# SmartWatch-BASIC-TOP.net
KiCad netlist of a schematic drawn in EAGLE
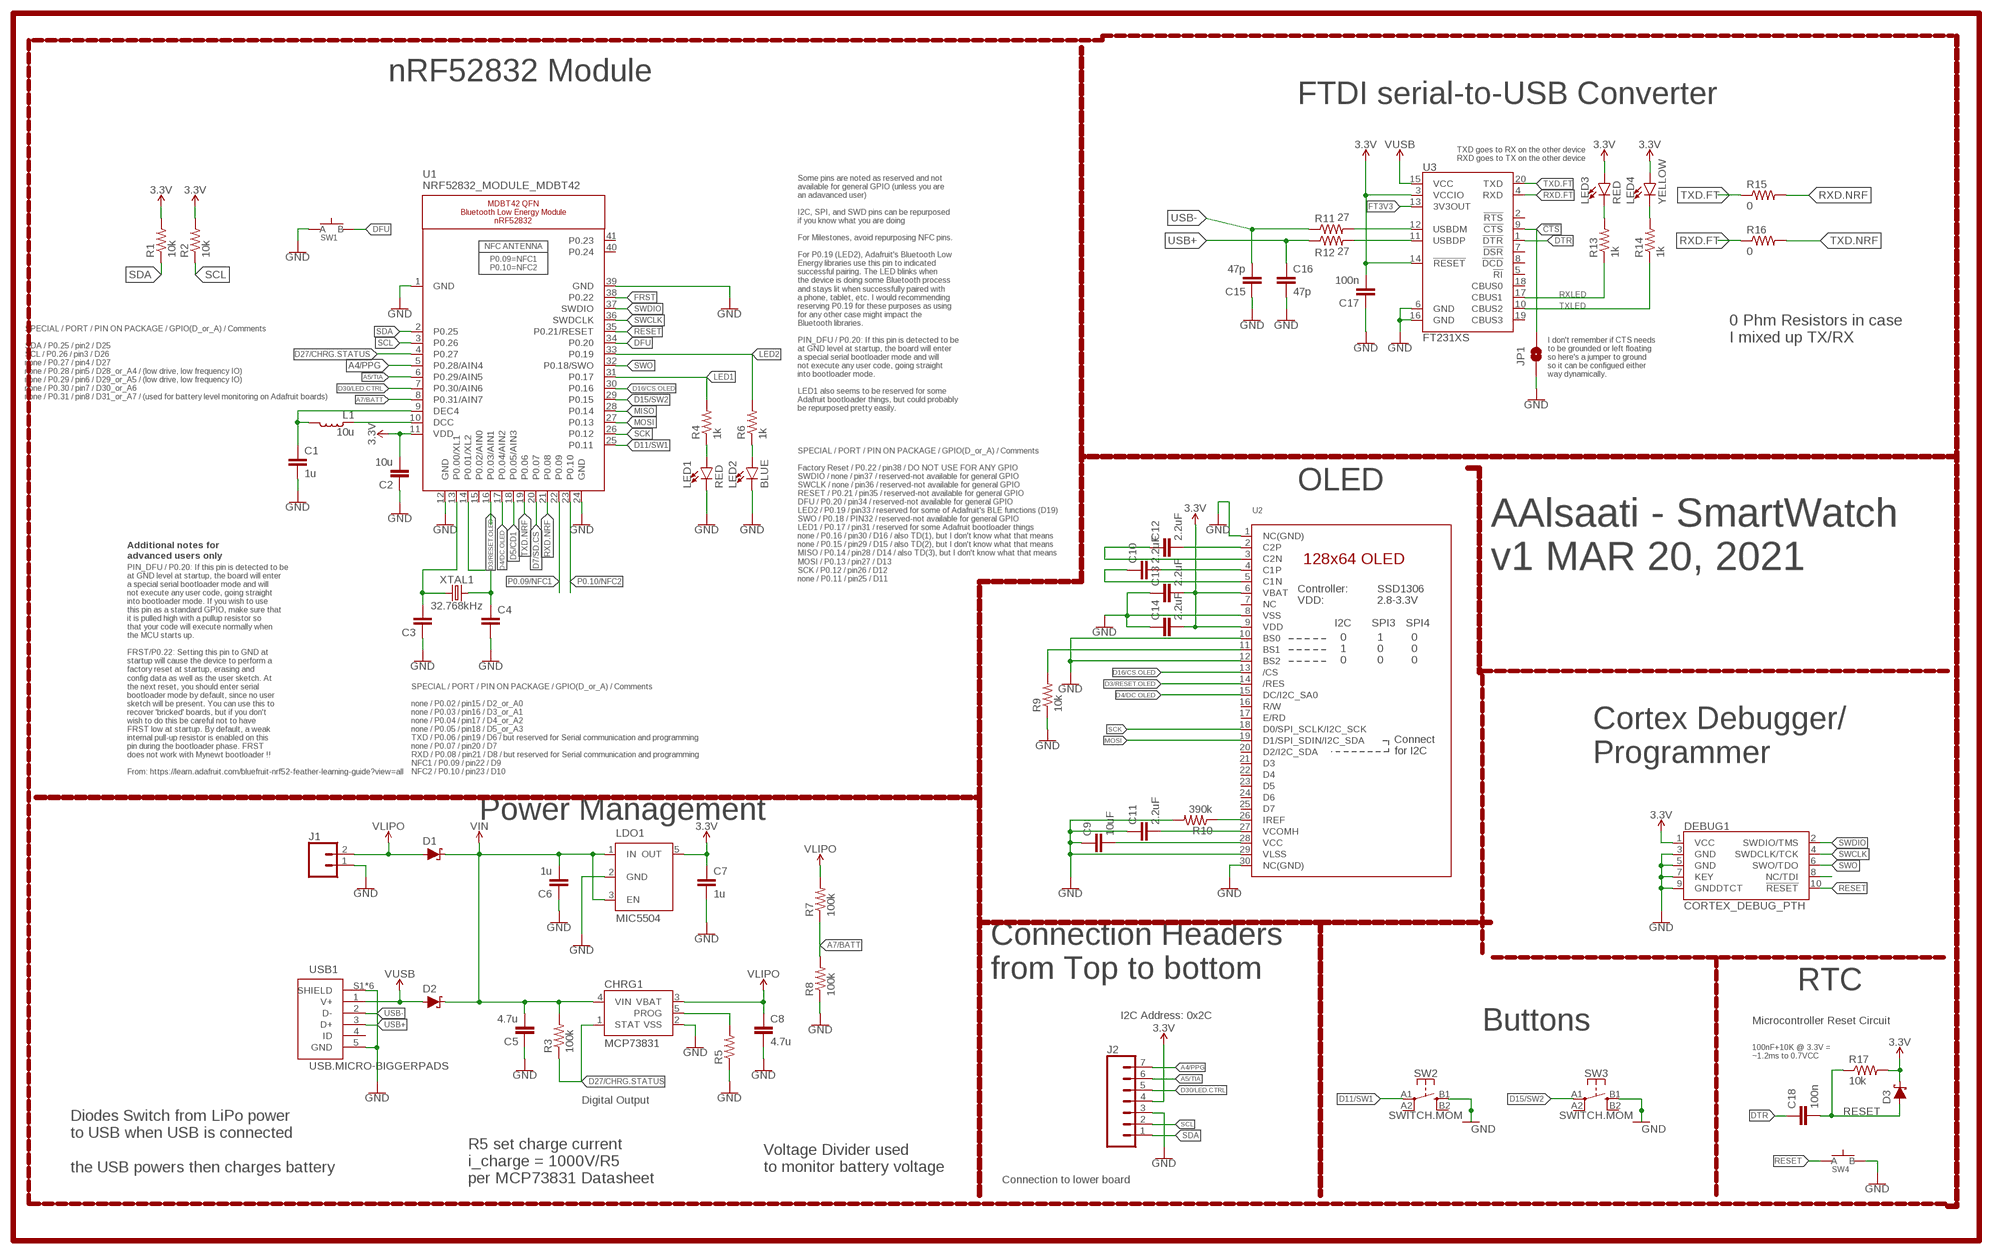
[diagram p0: schematic, sheet 1]

(export (version "E")
  (design (tool "Eeschema 10.0.6"))
  (components
    (comp (ref "C1")
      (value "1u")
      (footprint "eagle-import:C0603")
      (libsource (lib "eagle-import") (part "CAPACITOR0603"))
    )
    (comp (ref "C2")
      (value "10u")
      (footprint "eagle-import:C0805")
      (libsource (lib "eagle-import") (part "CAPACITOR0805"))
    )
    (comp (ref "C3")
      (value "CAPACITOR0603")
      (footprint "eagle-import:C0603")
      (libsource (lib "eagle-import") (part "CAPACITOR0603"))
    )
    (comp (ref "C4")
      (value "CAPACITOR0603")
      (footprint "eagle-import:C0603")
      (libsource (lib "eagle-import") (part "CAPACITOR0603"))
    )
    (comp (ref "C5")
      (value "4.7u")
      (footprint "eagle-import:C0603")
      (libsource (lib "eagle-import") (part "CAPACITOR0603"))
    )
    (comp (ref "C6")
      (value "1u")
      (footprint "eagle-import:C0603")
      (libsource (lib "eagle-import") (part "CAPACITOR0603"))
    )
    (comp (ref "C7")
      (value "1u")
      (footprint "eagle-import:C0603")
      (libsource (lib "eagle-import") (part "CAPACITOR0603"))
    )
    (comp (ref "C8")
      (value "4.7u")
      (footprint "eagle-import:C0603")
      (libsource (lib "eagle-import") (part "CAPACITOR0603"))
    )
    (comp (ref "C9")
      (value "10uF")
      (footprint "eagle-import:C0603")
      (libsource (lib "eagle-import") (part "CAPACITOR0603"))
    )
    (comp (ref "C10")
      (value "2.2uF")
      (footprint "eagle-import:C0402")
      (libsource (lib "eagle-import") (part "CAPACITOR0402"))
    )
    (comp (ref "C11")
      (value "2.2uF")
      (footprint "eagle-import:C0603")
      (libsource (lib "eagle-import") (part "CAPACITOR0603"))
    )
    (comp (ref "C12")
      (value "2.2uF")
      (footprint "eagle-import:C0402")
      (libsource (lib "eagle-import") (part "CAPACITOR0402"))
    )
    (comp (ref "C13")
      (value "2.2uF")
      (footprint "eagle-import:C0402")
      (libsource (lib "eagle-import") (part "CAPACITOR0402"))
    )
    (comp (ref "C14")
      (value "2.2uF")
      (footprint "eagle-import:C0402")
      (libsource (lib "eagle-import") (part "CAPACITOR0402"))
    )
    (comp (ref "C15")
      (value "47p")
      (footprint "eagle-import:C0603")
      (libsource (lib "eagle-import") (part "CAPACITOR0603"))
    )
    (comp (ref "C16")
      (value "47p")
      (footprint "eagle-import:C0603")
      (libsource (lib "eagle-import") (part "CAPACITOR0603"))
    )
    (comp (ref "C17")
      (value "100n")
      (footprint "eagle-import:C0603")
      (libsource (lib "eagle-import") (part "CAPACITOR0603"))
    )
    (comp (ref "C18")
      (value "100n")
      (footprint "eagle-import:C0603")
      (libsource (lib "eagle-import") (part "CAPACITOR0603"))
    )
    (comp (ref "CHRG1")
      (value "MCP73831")
      (footprint "eagle-import:SOT23-5")
      (libsource (lib "eagle-import") (part "MCP73831"))
    )
    (comp (ref "D1")
      (value "SCHOTTKY-USC")
      (footprint "eagle-import:USC")
      (libsource (lib "eagle-import") (part "SCHOTTKY-USC"))
    )
    (comp (ref "D2")
      (value "SCHOTTKY-USC")
      (footprint "eagle-import:USC")
      (libsource (lib "eagle-import") (part "SCHOTTKY-USC"))
    )
    (comp (ref "D3")
      (value "SCHOTTKY-USC")
      (footprint "eagle-import:USC")
      (libsource (lib "eagle-import") (part "SCHOTTKY-USC"))
    )
    (comp (ref "DEBUG1")
      (value "CORTEX_DEBUG_PTH")
      (footprint "eagle-import:2X5-PTH-1.27MM")
      (libsource (lib "eagle-import") (part "CORTEX_DEBUG_PTH"))
    )
    (comp (ref "J1")
      (value "CONN_02")
      (footprint "eagle-import:1X02")
      (libsource (lib "eagle-import") (part "CONN_02"))
    )
    (comp (ref "J2")
      (value "CONN_07-1.27MM")
      (footprint "eagle-import:1X07_1.27MM")
      (libsource (lib "eagle-import") (part "CONN_07-1.27MM"))
    )
    (comp (ref "JP1")
      (value "JUMPER-SMT_2_NO_SILK")
      (footprint "eagle-import:SMT-JUMPER_2_NO_SILK")
      (libsource (lib "eagle-import") (part "JUMPER-SMT_2_NO_SILK"))
    )
    (comp (ref "L1")
      (value "10u")
      (footprint "eagle-import:L0603")
      (libsource (lib "eagle-import") (part "INDUCTOR0603"))
    )
    (comp (ref "LDO1")
      (value "MIC5504")
      (footprint "eagle-import:SOT23-5")
      (libsource (lib "eagle-import") (part "MIC5504"))
    )
    (comp (ref "LED1")
      (value "RED")
      (footprint "eagle-import:LED-0603")
      (libsource (lib "eagle-import") (part "LED0603"))
    )
    (comp (ref "LED2")
      (value "BLUE")
      (footprint "eagle-import:LED-0603")
      (libsource (lib "eagle-import") (part "LED0603"))
    )
    (comp (ref "LED3")
      (value "RED")
      (footprint "eagle-import:LED-0603")
      (libsource (lib "eagle-import") (part "LED0603"))
    )
    (comp (ref "LED4")
      (value "YELLOW")
      (footprint "eagle-import:LED-0603")
      (libsource (lib "eagle-import") (part "LED0603"))
    )
    (comp (ref "R1")
      (value "10k")
      (footprint "eagle-import:R0603")
      (libsource (lib "eagle-import") (part "RESISTOR0603"))
    )
    (comp (ref "R2")
      (value "10k")
      (footprint "eagle-import:R0603")
      (libsource (lib "eagle-import") (part "RESISTOR0603"))
    )
    (comp (ref "R3")
      (value "100k")
      (footprint "eagle-import:R0603")
      (libsource (lib "eagle-import") (part "RESISTOR0603"))
    )
    (comp (ref "R4")
      (value "1k")
      (footprint "eagle-import:R0603")
      (libsource (lib "eagle-import") (part "RESISTOR0603"))
    )
    (comp (ref "R5")
      (value "RESISTOR0603")
      (footprint "eagle-import:R0603")
      (libsource (lib "eagle-import") (part "RESISTOR0603"))
    )
    (comp (ref "R6")
      (value "1k")
      (footprint "eagle-import:R0603")
      (libsource (lib "eagle-import") (part "RESISTOR0603"))
    )
    (comp (ref "R7")
      (value "100k")
      (footprint "eagle-import:R0603")
      (libsource (lib "eagle-import") (part "RESISTOR0603"))
    )
    (comp (ref "R8")
      (value "100k")
      (footprint "eagle-import:R0603")
      (libsource (lib "eagle-import") (part "RESISTOR0603"))
    )
    (comp (ref "R9")
      (value "10k")
      (footprint "eagle-import:R0603")
      (libsource (lib "eagle-import") (part "RESISTOR0603"))
    )
    (comp (ref "R10")
      (value "390k")
      (footprint "eagle-import:R0603")
      (libsource (lib "eagle-import") (part "RESISTOR0603"))
    )
    (comp (ref "R11")
      (value "27")
      (footprint "eagle-import:R0603")
      (libsource (lib "eagle-import") (part "RESISTOR0603"))
    )
    (comp (ref "R12")
      (value "27")
      (footprint "eagle-import:R0603")
      (libsource (lib "eagle-import") (part "RESISTOR0603"))
    )
    (comp (ref "R13")
      (value "1k")
      (footprint "eagle-import:R0603")
      (libsource (lib "eagle-import") (part "RESISTOR0603"))
    )
    (comp (ref "R14")
      (value "1k")
      (footprint "eagle-import:R0603")
      (libsource (lib "eagle-import") (part "RESISTOR0603"))
    )
    (comp (ref "R15")
      (value "0")
      (footprint "eagle-import:R0603")
      (libsource (lib "eagle-import") (part "RESISTOR0603"))
    )
    (comp (ref "R16")
      (value "0")
      (footprint "eagle-import:R0603")
      (libsource (lib "eagle-import") (part "RESISTOR0603"))
    )
    (comp (ref "R17")
      (value "10k")
      (footprint "eagle-import:R0603")
      (libsource (lib "eagle-import") (part "RESISTOR0603"))
    )
    (comp (ref "SW1")
      (value "SPST-PTS830GG140-COPY.1-3")
      (footprint "eagle-import:BUTTON-GULLWING")
      (libsource (lib "eagle-import") (part "SPST-PTS830GG140-COPY.1-3"))
    )
    (comp (ref "SW2")
      (value "SWITCH.MOM")
      (footprint "eagle-import:TACTILE_SWITCH_SMD_6.2MM_TALL")
      (libsource (lib "eagle-import") (part "SWITCH.MOM"))
    )
    (comp (ref "SW3")
      (value "SWITCH.MOM")
      (footprint "eagle-import:TACTILE_SWITCH_SMD_6.2MM_TALL")
      (libsource (lib "eagle-import") (part "SWITCH.MOM"))
    )
    (comp (ref "SW4")
      (value "SPST-PTS830GG140-COPY.1-3")
      (footprint "eagle-import:BUTTON-GULLWING")
      (libsource (lib "eagle-import") (part "SPST-PTS830GG140-COPY.1-3"))
    )
    (comp (ref "U1")
      (value "NRF52832_MODULE_MDBT42")
      (footprint "eagle-import:BLE_MODULE_RAYTAC_MDBT42")
      (libsource (lib "eagle-import") (part "NRF52832_MODULE_MDBT42"))
    )
    (comp (ref "U2")
      (value "DISP_OLED_UG-2864HSWEG01-NO-WRAPAROUND")
      (footprint "eagle-import:UG-2864HSWEG01_0.96IN_NO-WRAPAROUND")
      (libsource (lib "eagle-import") (part "DISP_OLED_UG-2864HSWEG01-NO-WRAPAROUND"))
    )
    (comp (ref "U3")
      (value "FT231XS")
      (footprint "eagle-import:SSOP20_L")
      (libsource (lib "eagle-import") (part "FT231XS"))
    )
    (comp (ref "USB1")
      (value "USB.MICRO-BIGGERPADS")
      (footprint "eagle-import:USB-MICRO-01.BIGGERPADS")
      (libsource (lib "eagle-import") (part "USB.MICRO-BIGGERPADS"))
    )
    (comp (ref "XTAL1")
      (value "32.768kHz")
      (footprint "eagle-import:2-SMD.NOLEAD.2.0MMTO1.2MM")
      (libsource (lib "eagle-import") (part "CRYSTALECS-.327-12.5-12-C-TR"))
    )
  )
  (nets
    (net (code "1") (name "/RXLED") (class "Default")
      (node (ref "R13") (pin "1") (pinfunction "1_1") (pintype "passive"))
      (node (ref "U3") (pin "17") (pinfunction "CBUS1_17") (pintype "bidirectional"))
    )
    (net (code "2") (name "/TXLED") (class "Default")
      (node (ref "R14") (pin "1") (pinfunction "1_1") (pintype "passive"))
      (node (ref "U3") (pin "10") (pinfunction "CBUS2_10") (pintype "bidirectional"))
    )
    (net (code "3") (name "/~{CTS}") (class "Default")
      (node (ref "JP1") (pin "2") (pinfunction "2_2") (pintype "passive"))
      (node (ref "U3") (pin "9") (pinfunction "~{CTS}_9") (pintype "bidirectional"))
    )
    (net (code "4") (name "3.3V") (class "Default")
      (node (ref "C13") (pin "2") (pinfunction "2_2") (pintype "passive"))
      (node (ref "C14") (pin "2") (pinfunction "2_2") (pintype "passive"))
      (node (ref "C17") (pin "2") (pinfunction "2_2") (pintype "passive"))
      (node (ref "C2") (pin "2") (pinfunction "2_2") (pintype "passive"))
      (node (ref "C7") (pin "1") (pinfunction "1_1") (pintype "passive"))
      (node (ref "D3") (pin "-") (pinfunction "C_-") (pintype "passive"))
      (node (ref "DEBUG1") (pin "1") (pinfunction "VCC_1") (pintype "bidirectional"))
      (node (ref "J2") (pin "4") (pinfunction "4_4") (pintype "passive"))
      (node (ref "LDO1") (pin "5") (pinfunction "OUT_5") (pintype "bidirectional"))
      (node (ref "LED3") (pin "A") (pinfunction "A_A") (pintype "passive"))
      (node (ref "LED4") (pin "A") (pinfunction "A_A") (pintype "passive"))
      (node (ref "R1") (pin "2") (pinfunction "2_2") (pintype "passive"))
      (node (ref "R17") (pin "2") (pinfunction "2_2") (pintype "passive"))
      (node (ref "R2") (pin "2") (pinfunction "2_2") (pintype "passive"))
      (node (ref "U1") (pin "11") (pinfunction "VDD_11") (pintype "bidirectional"))
      (node (ref "U2") (pin "6") (pinfunction "VBAT_6") (pintype "input"))
      (node (ref "U2") (pin "9") (pinfunction "VDD_9") (pintype "power_in"))
      (node (ref "U3") (pin "14") (pinfunction "~{RESET}_14") (pintype "bidirectional"))
      (node (ref "U3") (pin "3") (pinfunction "VCCIO_3") (pintype "bidirectional"))
    )
    (net (code "5") (name "A4{slash}PPG") (class "Default")
      (node (ref "J2") (pin "7") (pinfunction "7_7") (pintype "passive"))
      (node (ref "U1") (pin "5") (pinfunction "P0.28/AIN4_5") (pintype "bidirectional"))
    )
    (net (code "6") (name "A5{slash}TIA") (class "Default")
      (node (ref "J2") (pin "6") (pinfunction "6_6") (pintype "passive"))
      (node (ref "U1") (pin "6") (pinfunction "P0.29/AIN5_6") (pintype "bidirectional"))
    )
    (net (code "7") (name "A7{slash}BATT") (class "Default")
      (node (ref "R7") (pin "1") (pinfunction "1_1") (pintype "passive"))
      (node (ref "R8") (pin "2") (pinfunction "2_2") (pintype "passive"))
      (node (ref "U1") (pin "8") (pinfunction "P0.31/AIN7_8") (pintype "bidirectional"))
    )
    (net (code "8") (name "D3{slash}RESET.OLED") (class "Default")
      (node (ref "U1") (pin "16") (pinfunction "P0.03/AIN1_16") (pintype "bidirectional"))
      (node (ref "U2") (pin "14") (pinfunction "/RES_14") (pintype "input"))
    )
    (net (code "9") (name "D4{slash}DC.OLED") (class "Default")
      (node (ref "U1") (pin "17") (pinfunction "P0.04/AIN2_17") (pintype "bidirectional"))
      (node (ref "U2") (pin "15") (pinfunction "DC/I2C_SA0_15") (pintype "input"))
    )
    (net (code "10") (name "D5{slash}CD1") (class "Default")
      (node (ref "U1") (pin "18") (pinfunction "P0.05/AIN3_18") (pintype "bidirectional"))
    )
    (net (code "11") (name "D7{slash}SD.CS") (class "Default")
      (node (ref "U1") (pin "20") (pinfunction "P0.07_20") (pintype "bidirectional"))
    )
    (net (code "12") (name "D11{slash}SW1") (class "Default")
      (node (ref "SW2") (pin "A1") (pinfunction "1_A1") (pintype "passive"))
      (node (ref "U1") (pin "25") (pinfunction "P0.11_25") (pintype "bidirectional"))
    )
    (net (code "13") (name "D15{slash}SW2") (class "Default")
      (node (ref "SW3") (pin "A1") (pinfunction "1_A1") (pintype "passive"))
      (node (ref "U1") (pin "29") (pinfunction "P0.15_29") (pintype "bidirectional"))
    )
    (net (code "14") (name "D16{slash}CS.OLED") (class "Default")
      (node (ref "U1") (pin "30") (pinfunction "P0.16_30") (pintype "bidirectional"))
      (node (ref "U2") (pin "13") (pinfunction "/CS_13") (pintype "input"))
    )
    (net (code "15") (name "D27{slash}CHRG.STATUS") (class "Default")
      (node (ref "CHRG1") (pin "1") (pinfunction "STAT_1") (pintype "output"))
      (node (ref "R3") (pin "1") (pinfunction "1_1") (pintype "passive"))
      (node (ref "U1") (pin "4") (pinfunction "P0.27_4") (pintype "bidirectional"))
    )
    (net (code "16") (name "D30{slash}LED.CTRL") (class "Default")
      (node (ref "J2") (pin "5") (pinfunction "5_5") (pintype "passive"))
      (node (ref "U1") (pin "7") (pinfunction "P0.30/AIN6_7") (pintype "bidirectional"))
    )
    (net (code "17") (name "DFU") (class "Default")
      (node (ref "SW1") (pin "3") (pinfunction "B_3") (pintype "bidirectional"))
      (node (ref "U1") (pin "34") (pinfunction "P0.20_34") (pintype "bidirectional"))
    )
    (net (code "18") (name "DTR") (class "Default")
      (node (ref "C18") (pin "1") (pinfunction "1_1") (pintype "passive"))
      (node (ref "U3") (pin "1") (pinfunction "~{DTR}_1") (pintype "bidirectional"))
    )
    (net (code "19") (name "FRST") (class "Default")
      (node (ref "U1") (pin "38") (pinfunction "P0.22_38") (pintype "bidirectional"))
    )
    (net (code "20") (name "FT3V3") (class "Default")
      (node (ref "U3") (pin "13") (pinfunction "3V3OUT_13") (pintype "bidirectional"))
    )
    (net (code "21") (name "GND") (class "Default")
      (node (ref "C1") (pin "2") (pinfunction "2_2") (pintype "passive"))
      (node (ref "C11") (pin "1") (pinfunction "1_1") (pintype "passive"))
      (node (ref "C13") (pin "1") (pinfunction "1_1") (pintype "passive"))
      (node (ref "C14") (pin "1") (pinfunction "1_1") (pintype "passive"))
      (node (ref "C15") (pin "1") (pinfunction "1_1") (pintype "passive"))
      (node (ref "C16") (pin "2") (pinfunction "2_2") (pintype "passive"))
      (node (ref "C17") (pin "1") (pinfunction "1_1") (pintype "passive"))
      (node (ref "C2") (pin "1") (pinfunction "1_1") (pintype "passive"))
      (node (ref "C3") (pin "1") (pinfunction "1_1") (pintype "passive"))
      (node (ref "C4") (pin "2") (pinfunction "2_2") (pintype "passive"))
      (node (ref "C5") (pin "1") (pinfunction "1_1") (pintype "passive"))
      (node (ref "C6") (pin "1") (pinfunction "1_1") (pintype "passive"))
      (node (ref "C7") (pin "2") (pinfunction "2_2") (pintype "passive"))
      (node (ref "C8") (pin "2") (pinfunction "2_2") (pintype "passive"))
      (node (ref "C9") (pin "1") (pinfunction "1_1") (pintype "passive"))
      (node (ref "CHRG1") (pin "2") (pinfunction "VSS_2") (pintype "power_in"))
      (node (ref "DEBUG1") (pin "3") (pinfunction "GND_3") (pintype "bidirectional"))
      (node (ref "DEBUG1") (pin "5") (pinfunction "GND_5") (pintype "bidirectional"))
      (node (ref "DEBUG1") (pin "7") (pinfunction "KEY_7") (pintype "bidirectional"))
      (node (ref "DEBUG1") (pin "9") (pinfunction "GNDDTCT_9") (pintype "bidirectional"))
      (node (ref "J1") (pin "1") (pinfunction "1_1") (pintype "passive"))
      (node (ref "J2") (pin "3") (pinfunction "3_3") (pintype "passive"))
      (node (ref "JP1") (pin "1") (pinfunction "1_1") (pintype "passive"))
      (node (ref "LDO1") (pin "2") (pinfunction "GND_2") (pintype "bidirectional"))
      (node (ref "LED1") (pin "C") (pinfunction "C_C") (pintype "passive"))
      (node (ref "LED2") (pin "C") (pinfunction "C_C") (pintype "passive"))
      (node (ref "R10") (pin "2") (pinfunction "2_2") (pintype "passive"))
      (node (ref "R5") (pin "1") (pinfunction "1_1") (pintype "passive"))
      (node (ref "R8") (pin "1") (pinfunction "1_1") (pintype "passive"))
      (node (ref "R9") (pin "1") (pinfunction "1_1") (pintype "passive"))
      (node (ref "SW1") (pin "1") (pinfunction "A_1") (pintype "bidirectional"))
      (node (ref "SW2") (pin "B1") (pinfunction "3_B1") (pintype "passive"))
      (node (ref "SW3") (pin "B1") (pinfunction "3_B1") (pintype "passive"))
      (node (ref "SW4") (pin "3") (pinfunction "B_3") (pintype "bidirectional"))
      (node (ref "U1") (pin "1") (pinfunction "GND_1") (pintype "bidirectional"))
      (node (ref "U1") (pin "12") (pinfunction "GND_12") (pintype "bidirectional"))
      (node (ref "U1") (pin "24") (pinfunction "GND_24") (pintype "bidirectional"))
      (node (ref "U1") (pin "39") (pinfunction "GND_39") (pintype "bidirectional"))
      (node (ref "U2") (pin "1") (pinfunction "NC(GND)_1") (pintype "input"))
      (node (ref "U2") (pin "10") (pinfunction "BS0_10") (pintype "input"))
      (node (ref "U2") (pin "12") (pinfunction "BS2_12") (pintype "input"))
      (node (ref "U2") (pin "29") (pinfunction "VLSS_29") (pintype "power_in"))
      (node (ref "U2") (pin "30") (pinfunction "NC(GND)_30") (pintype "input"))
      (node (ref "U2") (pin "8") (pinfunction "VSS_8") (pintype "power_in"))
      (node (ref "U3") (pin "16") (pinfunction "GND_16") (pintype "bidirectional"))
      (node (ref "U3") (pin "6") (pinfunction "GND_6") (pintype "bidirectional"))
      (node (ref "USB1") (pin "5") (pinfunction "GND_5") (pintype "bidirectional"))
      (node (ref "USB1") (pin "S1") (pinfunction "SHIELD_S1") (pintype "bidirectional"))
      (node (ref "USB1") (pin "S2") (pinfunction "SHIELD_S2") (pintype "bidirectional"))
      (node (ref "USB1") (pin "S3") (pinfunction "SHIELD_S3") (pintype "bidirectional"))
      (node (ref "USB1") (pin "S4") (pinfunction "SHIELD_S4") (pintype "bidirectional"))
      (node (ref "USB1") (pin "S5") (pinfunction "SHIELD_S5") (pintype "bidirectional"))
      (node (ref "USB1") (pin "S6") (pinfunction "SHIELD_S6") (pintype "bidirectional"))
    )
    (net (code "22") (name "LED1") (class "Default")
      (node (ref "R4") (pin "2") (pinfunction "2_2") (pintype "passive"))
      (node (ref "U1") (pin "31") (pinfunction "P0.17_31") (pintype "bidirectional"))
    )
    (net (code "23") (name "LED2") (class "Default")
      (node (ref "R6") (pin "2") (pinfunction "2_2") (pintype "passive"))
      (node (ref "U1") (pin "33") (pinfunction "P0.19_33") (pintype "bidirectional"))
    )
    (net (code "24") (name "MISO") (class "Default")
      (node (ref "U1") (pin "28") (pinfunction "P0.14_28") (pintype "bidirectional"))
    )
    (net (code "25") (name "MOSI") (class "Default")
      (node (ref "U1") (pin "27") (pinfunction "P0.13_27") (pintype "bidirectional"))
      (node (ref "U2") (pin "19") (pinfunction "D1/SPI_SDIN/I2C_SDA_19") (pintype "bidirectional"))
    )
    (net (code "26") (name "Net-(CHRG1-PROG)") (class "Default")
      (node (ref "CHRG1") (pin "5") (pinfunction "PROG_5") (pintype "input"))
      (node (ref "R5") (pin "2") (pinfunction "2_2") (pintype "passive"))
    )
    (net (code "27") (name "Net-(LED1-PadA)") (class "Default")
      (node (ref "LED1") (pin "A") (pinfunction "A_A") (pintype "passive"))
      (node (ref "R4") (pin "1") (pinfunction "1_1") (pintype "passive"))
    )
    (net (code "28") (name "Net-(LED2-PadA)") (class "Default")
      (node (ref "LED2") (pin "A") (pinfunction "A_A") (pintype "passive"))
      (node (ref "R6") (pin "1") (pinfunction "1_1") (pintype "passive"))
    )
    (net (code "29") (name "Net-(LED3-PadC)") (class "Default")
      (node (ref "LED3") (pin "C") (pinfunction "C_C") (pintype "passive"))
      (node (ref "R13") (pin "2") (pinfunction "2_2") (pintype "passive"))
    )
    (net (code "30") (name "Net-(LED4-PadC)") (class "Default")
      (node (ref "LED4") (pin "C") (pinfunction "C_C") (pintype "passive"))
      (node (ref "R14") (pin "2") (pinfunction "2_2") (pintype "passive"))
    )
    (net (code "31") (name "Net-(U1-DCC)") (class "Default")
      (node (ref "L1") (pin "1") (pinfunction "1_1") (pintype "passive"))
      (node (ref "U1") (pin "10") (pinfunction "DCC_10") (pintype "bidirectional"))
    )
    (net (code "32") (name "Net-(U1-DEC4)") (class "Default")
      (node (ref "C1") (pin "1") (pinfunction "1_1") (pintype "passive"))
      (node (ref "L1") (pin "2") (pinfunction "2_2") (pintype "passive"))
      (node (ref "U1") (pin "9") (pinfunction "DEC4_9") (pintype "bidirectional"))
    )
    (net (code "33") (name "Net-(U1-P0.00{slash}XL1)") (class "Default")
      (node (ref "C3") (pin "2") (pinfunction "2_2") (pintype "passive"))
      (node (ref "U1") (pin "13") (pinfunction "P0.00/XL1_13") (pintype "bidirectional"))
      (node (ref "XTAL1") (pin "P$1") (pinfunction "1_P$1") (pintype "passive"))
    )
    (net (code "34") (name "Net-(U1-P0.01{slash}XL2)") (class "Default")
      (node (ref "C4") (pin "1") (pinfunction "1_1") (pintype "passive"))
      (node (ref "U1") (pin "14") (pinfunction "P0.01/XL2_14") (pintype "bidirectional"))
      (node (ref "XTAL1") (pin "P$2") (pinfunction "2_P$2") (pintype "passive"))
    )
    (net (code "35") (name "Net-(U2-BS1)") (class "Default")
      (node (ref "R9") (pin "2") (pinfunction "2_2") (pintype "passive"))
      (node (ref "U2") (pin "11") (pinfunction "BS1_11") (pintype "input"))
    )
    (net (code "36") (name "Net-(U2-C1N)") (class "Default")
      (node (ref "C10") (pin "1") (pinfunction "1_1") (pintype "passive"))
      (node (ref "U2") (pin "5") (pinfunction "C1N_5") (pintype "input"))
    )
    (net (code "37") (name "Net-(U2-C1P)") (class "Default")
      (node (ref "C10") (pin "2") (pinfunction "2_2") (pintype "passive"))
      (node (ref "U2") (pin "4") (pinfunction "C1P_4") (pintype "input"))
    )
    (net (code "38") (name "Net-(U2-C2N)") (class "Default")
      (node (ref "C12") (pin "1") (pinfunction "1_1") (pintype "passive"))
      (node (ref "U2") (pin "3") (pinfunction "C2N_3") (pintype "input"))
    )
    (net (code "39") (name "Net-(U2-C2P)") (class "Default")
      (node (ref "C12") (pin "2") (pinfunction "2_2") (pintype "passive"))
      (node (ref "U2") (pin "2") (pinfunction "C2P_2") (pintype "input"))
    )
    (net (code "40") (name "Net-(U2-IREF)") (class "Default")
      (node (ref "R10") (pin "1") (pinfunction "1_1") (pintype "passive"))
      (node (ref "U2") (pin "26") (pinfunction "IREF_26") (pintype "input"))
    )
    (net (code "41") (name "Net-(U2-VCC)") (class "Default")
      (node (ref "C9") (pin "2") (pinfunction "2_2") (pintype "passive"))
      (node (ref "U2") (pin "28") (pinfunction "VCC_28") (pintype "power_in"))
    )
    (net (code "42") (name "Net-(U2-VCOMH)") (class "Default")
      (node (ref "C11") (pin "2") (pinfunction "2_2") (pintype "passive"))
      (node (ref "U2") (pin "27") (pinfunction "VCOMH_27") (pintype "output"))
    )
    (net (code "43") (name "Net-(U3-USBDM)") (class "Default")
      (node (ref "R11") (pin "2") (pinfunction "2_2") (pintype "passive"))
      (node (ref "U3") (pin "12") (pinfunction "USBDM_12") (pintype "bidirectional"))
    )
    (net (code "44") (name "Net-(U3-USBDP)") (class "Default")
      (node (ref "R12") (pin "2") (pinfunction "2_2") (pintype "passive"))
      (node (ref "U3") (pin "11") (pinfunction "USBDP_11") (pintype "bidirectional"))
    )
    (net (code "45") (name "P0.09{slash}NFC1") (class "Default")
      (node (ref "U1") (pin "22") (pinfunction "P0.09_22") (pintype "bidirectional"))
    )
    (net (code "46") (name "P0.10{slash}NFC2") (class "Default")
      (node (ref "U1") (pin "23") (pinfunction "P0.10_23") (pintype "bidirectional"))
    )
    (net (code "47") (name "RESET") (class "Default")
      (node (ref "C18") (pin "2") (pinfunction "2_2") (pintype "passive"))
      (node (ref "D3") (pin "+") (pinfunction "A_+") (pintype "passive"))
      (node (ref "DEBUG1") (pin "10") (pinfunction "~{RESET}_10") (pintype "bidirectional"))
      (node (ref "R17") (pin "1") (pinfunction "1_1") (pintype "passive"))
      (node (ref "SW4") (pin "1") (pinfunction "A_1") (pintype "bidirectional"))
      (node (ref "U1") (pin "35") (pinfunction "P0.21/RESET_35") (pintype "bidirectional"))
    )
    (net (code "48") (name "RXD.FT") (class "Default")
      (node (ref "R16") (pin "1") (pinfunction "1_1") (pintype "passive"))
      (node (ref "U3") (pin "4") (pinfunction "RXD_4") (pintype "bidirectional"))
    )
    (net (code "49") (name "RXD.NRF") (class "Default")
      (node (ref "R15") (pin "2") (pinfunction "2_2") (pintype "passive"))
      (node (ref "U1") (pin "21") (pinfunction "P0.08_21") (pintype "bidirectional"))
    )
    (net (code "50") (name "SCK") (class "Default")
      (node (ref "U1") (pin "26") (pinfunction "P0.12_26") (pintype "bidirectional"))
      (node (ref "U2") (pin "18") (pinfunction "D0/SPI_SCLK/I2C_SCK_18") (pintype "bidirectional"))
    )
    (net (code "51") (name "SCL") (class "Default")
      (node (ref "J2") (pin "2") (pinfunction "2_2") (pintype "passive"))
      (node (ref "R2") (pin "1") (pinfunction "1_1") (pintype "passive"))
      (node (ref "U1") (pin "3") (pinfunction "P0.26_3") (pintype "bidirectional"))
    )
    (net (code "52") (name "SDA") (class "Default")
      (node (ref "J2") (pin "1") (pinfunction "1_1") (pintype "passive"))
      (node (ref "R1") (pin "1") (pinfunction "1_1") (pintype "passive"))
      (node (ref "U1") (pin "2") (pinfunction "P0.25_2") (pintype "bidirectional"))
    )
    (net (code "53") (name "SWCLK") (class "Default")
      (node (ref "DEBUG1") (pin "4") (pinfunction "SWDCLK/TCK_4") (pintype "bidirectional"))
      (node (ref "U1") (pin "36") (pinfunction "SWDCLK_36") (pintype "bidirectional"))
    )
    (net (code "54") (name "SWDIO") (class "Default")
      (node (ref "DEBUG1") (pin "2") (pinfunction "SWDIO/TMS_2") (pintype "bidirectional"))
      (node (ref "U1") (pin "37") (pinfunction "SWDIO_37") (pintype "bidirectional"))
    )
    (net (code "55") (name "SWO") (class "Default")
      (node (ref "DEBUG1") (pin "6") (pinfunction "SWO/TDO_6") (pintype "bidirectional"))
      (node (ref "U1") (pin "32") (pinfunction "P0.18/SWO_32") (pintype "bidirectional"))
    )
    (net (code "56") (name "TXD.FT") (class "Default")
      (node (ref "R15") (pin "1") (pinfunction "1_1") (pintype "passive"))
      (node (ref "U3") (pin "20") (pinfunction "TXD_20") (pintype "bidirectional"))
    )
    (net (code "57") (name "TXD.NRF") (class "Default")
      (node (ref "R16") (pin "2") (pinfunction "2_2") (pintype "passive"))
      (node (ref "U1") (pin "19") (pinfunction "P0.06_19") (pintype "bidirectional"))
    )
    (net (code "58") (name "USB+") (class "Default")
      (node (ref "C16") (pin "1") (pinfunction "1_1") (pintype "passive"))
      (node (ref "R12") (pin "1") (pinfunction "1_1") (pintype "passive"))
      (node (ref "USB1") (pin "3") (pinfunction "D+_3") (pintype "bidirectional"))
    )
    (net (code "59") (name "USB-") (class "Default")
      (node (ref "C15") (pin "2") (pinfunction "2_2") (pintype "passive"))
      (node (ref "R11") (pin "1") (pinfunction "1_1") (pintype "passive"))
      (node (ref "USB1") (pin "2") (pinfunction "D-_2") (pintype "bidirectional"))
    )
    (net (code "60") (name "VIN") (class "Default")
      (node (ref "C5") (pin "2") (pinfunction "2_2") (pintype "passive"))
      (node (ref "C6") (pin "2") (pinfunction "2_2") (pintype "passive"))
      (node (ref "CHRG1") (pin "4") (pinfunction "VIN_4") (pintype "power_in"))
      (node (ref "D1") (pin "-") (pinfunction "C_-") (pintype "passive"))
      (node (ref "D2") (pin "-") (pinfunction "C_-") (pintype "passive"))
      (node (ref "LDO1") (pin "1") (pinfunction "IN_1") (pintype "bidirectional"))
      (node (ref "LDO1") (pin "3") (pinfunction "EN_3") (pintype "bidirectional"))
      (node (ref "R3") (pin "2") (pinfunction "2_2") (pintype "passive"))
    )
    (net (code "61") (name "VLIPO") (class "Default")
      (node (ref "C8") (pin "1") (pinfunction "1_1") (pintype "passive"))
      (node (ref "CHRG1") (pin "3") (pinfunction "VBAT_3") (pintype "power_in"))
      (node (ref "D1") (pin "+") (pinfunction "A_+") (pintype "passive"))
      (node (ref "J1") (pin "2") (pinfunction "2_2") (pintype "passive"))
      (node (ref "R7") (pin "2") (pinfunction "2_2") (pintype "passive"))
    )
    (net (code "62") (name "VUSB") (class "Default")
      (node (ref "D2") (pin "+") (pinfunction "A_+") (pintype "passive"))
      (node (ref "U3") (pin "15") (pinfunction "VCC_15") (pintype "bidirectional"))
      (node (ref "USB1") (pin "1") (pinfunction "V+_1") (pintype "bidirectional"))
    )
    (net (code "63") (name "unconnected-(DEBUG1-NC{slash}TDI-Pad8)") (class "Default")
      (node (ref "DEBUG1") (pin "8") (pinfunction "NC/TDI_8") (pintype "bidirectional"))
    )
    (net (code "64") (name "unconnected-(SW2-2-PadA2)") (class "Default")
      (node (ref "SW2") (pin "A2") (pinfunction "2_A2") (pintype "passive"))
    )
    (net (code "65") (name "unconnected-(SW2-4-PadB2)") (class "Default")
      (node (ref "SW2") (pin "B2") (pinfunction "4_B2") (pintype "passive"))
    )
    (net (code "66") (name "unconnected-(SW3-2-PadA2)") (class "Default")
      (node (ref "SW3") (pin "A2") (pinfunction "2_A2") (pintype "passive"))
    )
    (net (code "67") (name "unconnected-(SW3-4-PadB2)") (class "Default")
      (node (ref "SW3") (pin "B2") (pinfunction "4_B2") (pintype "passive"))
    )
    (net (code "68") (name "unconnected-(U1-P0.02{slash}AIN0-Pad15)") (class "Default")
      (node (ref "U1") (pin "15") (pinfunction "P0.02/AIN0_15") (pintype "bidirectional"))
    )
    (net (code "69") (name "unconnected-(U1-P0.23-Pad41)") (class "Default")
      (node (ref "U1") (pin "41") (pinfunction "P0.23_41") (pintype "bidirectional"))
    )
    (net (code "70") (name "unconnected-(U1-P0.24-Pad40)") (class "Default")
      (node (ref "U1") (pin "40") (pinfunction "P0.24_40") (pintype "bidirectional"))
    )
    (net (code "71") (name "unconnected-(U2-D2{slash}I2C_SDA-Pad20)") (class "Default")
      (node (ref "U2") (pin "20") (pinfunction "D2/I2C_SDA_20") (pintype "bidirectional"))
    )
    (net (code "72") (name "unconnected-(U2-D3-Pad21)") (class "Default")
      (node (ref "U2") (pin "21") (pinfunction "D3_21") (pintype "bidirectional"))
    )
    (net (code "73") (name "unconnected-(U2-D4-Pad22)") (class "Default")
      (node (ref "U2") (pin "22") (pinfunction "D4_22") (pintype "bidirectional"))
    )
    (net (code "74") (name "unconnected-(U2-D5-Pad23)") (class "Default")
      (node (ref "U2") (pin "23") (pinfunction "D5_23") (pintype "bidirectional"))
    )
    (net (code "75") (name "unconnected-(U2-D6-Pad24)") (class "Default")
      (node (ref "U2") (pin "24") (pinfunction "D6_24") (pintype "bidirectional"))
    )
    (net (code "76") (name "unconnected-(U2-D7-Pad25)") (class "Default")
      (node (ref "U2") (pin "25") (pinfunction "D7_25") (pintype "bidirectional"))
    )
    (net (code "77") (name "unconnected-(U2-E{slash}RD-Pad17)") (class "Default")
      (node (ref "U2") (pin "17") (pinfunction "E/RD_17") (pintype "input"))
    )
    (net (code "78") (name "unconnected-(U2-NC-Pad7)") (class "Default")
      (node (ref "U2") (pin "7") (pinfunction "NC_7") (pintype "no_connect"))
    )
    (net (code "79") (name "unconnected-(U2-R{slash}W-Pad16)") (class "Default")
      (node (ref "U2") (pin "16") (pinfunction "R/W_16") (pintype "input"))
    )
    (net (code "80") (name "unconnected-(U3-CBUS0-Pad18)") (class "Default")
      (node (ref "U3") (pin "18") (pinfunction "CBUS0_18") (pintype "bidirectional"))
    )
    (net (code "81") (name "unconnected-(U3-CBUS3-Pad19)") (class "Default")
      (node (ref "U3") (pin "19") (pinfunction "CBUS3_19") (pintype "bidirectional"))
    )
    (net (code "82") (name "unconnected-(U3-~{DCD}-Pad8)") (class "Default")
      (node (ref "U3") (pin "8") (pinfunction "~{DCD}_8") (pintype "bidirectional"))
    )
    (net (code "83") (name "unconnected-(U3-~{DSR}-Pad7)") (class "Default")
      (node (ref "U3") (pin "7") (pinfunction "~{DSR}_7") (pintype "bidirectional"))
    )
    (net (code "84") (name "unconnected-(U3-~{RI}-Pad5)") (class "Default")
      (node (ref "U3") (pin "5") (pinfunction "~{RI}_5") (pintype "bidirectional"))
    )
    (net (code "85") (name "unconnected-(U3-~{RTS}-Pad2)") (class "Default")
      (node (ref "U3") (pin "2") (pinfunction "~{RTS}_2") (pintype "bidirectional"))
    )
    (net (code "86") (name "unconnected-(USB1-ID-Pad4)") (class "Default")
      (node (ref "USB1") (pin "4") (pinfunction "ID_4") (pintype "bidirectional"))
    )
  )
)
